# dwengo-1_1.net
KiCad netlist of a schematic drawn in EAGLE
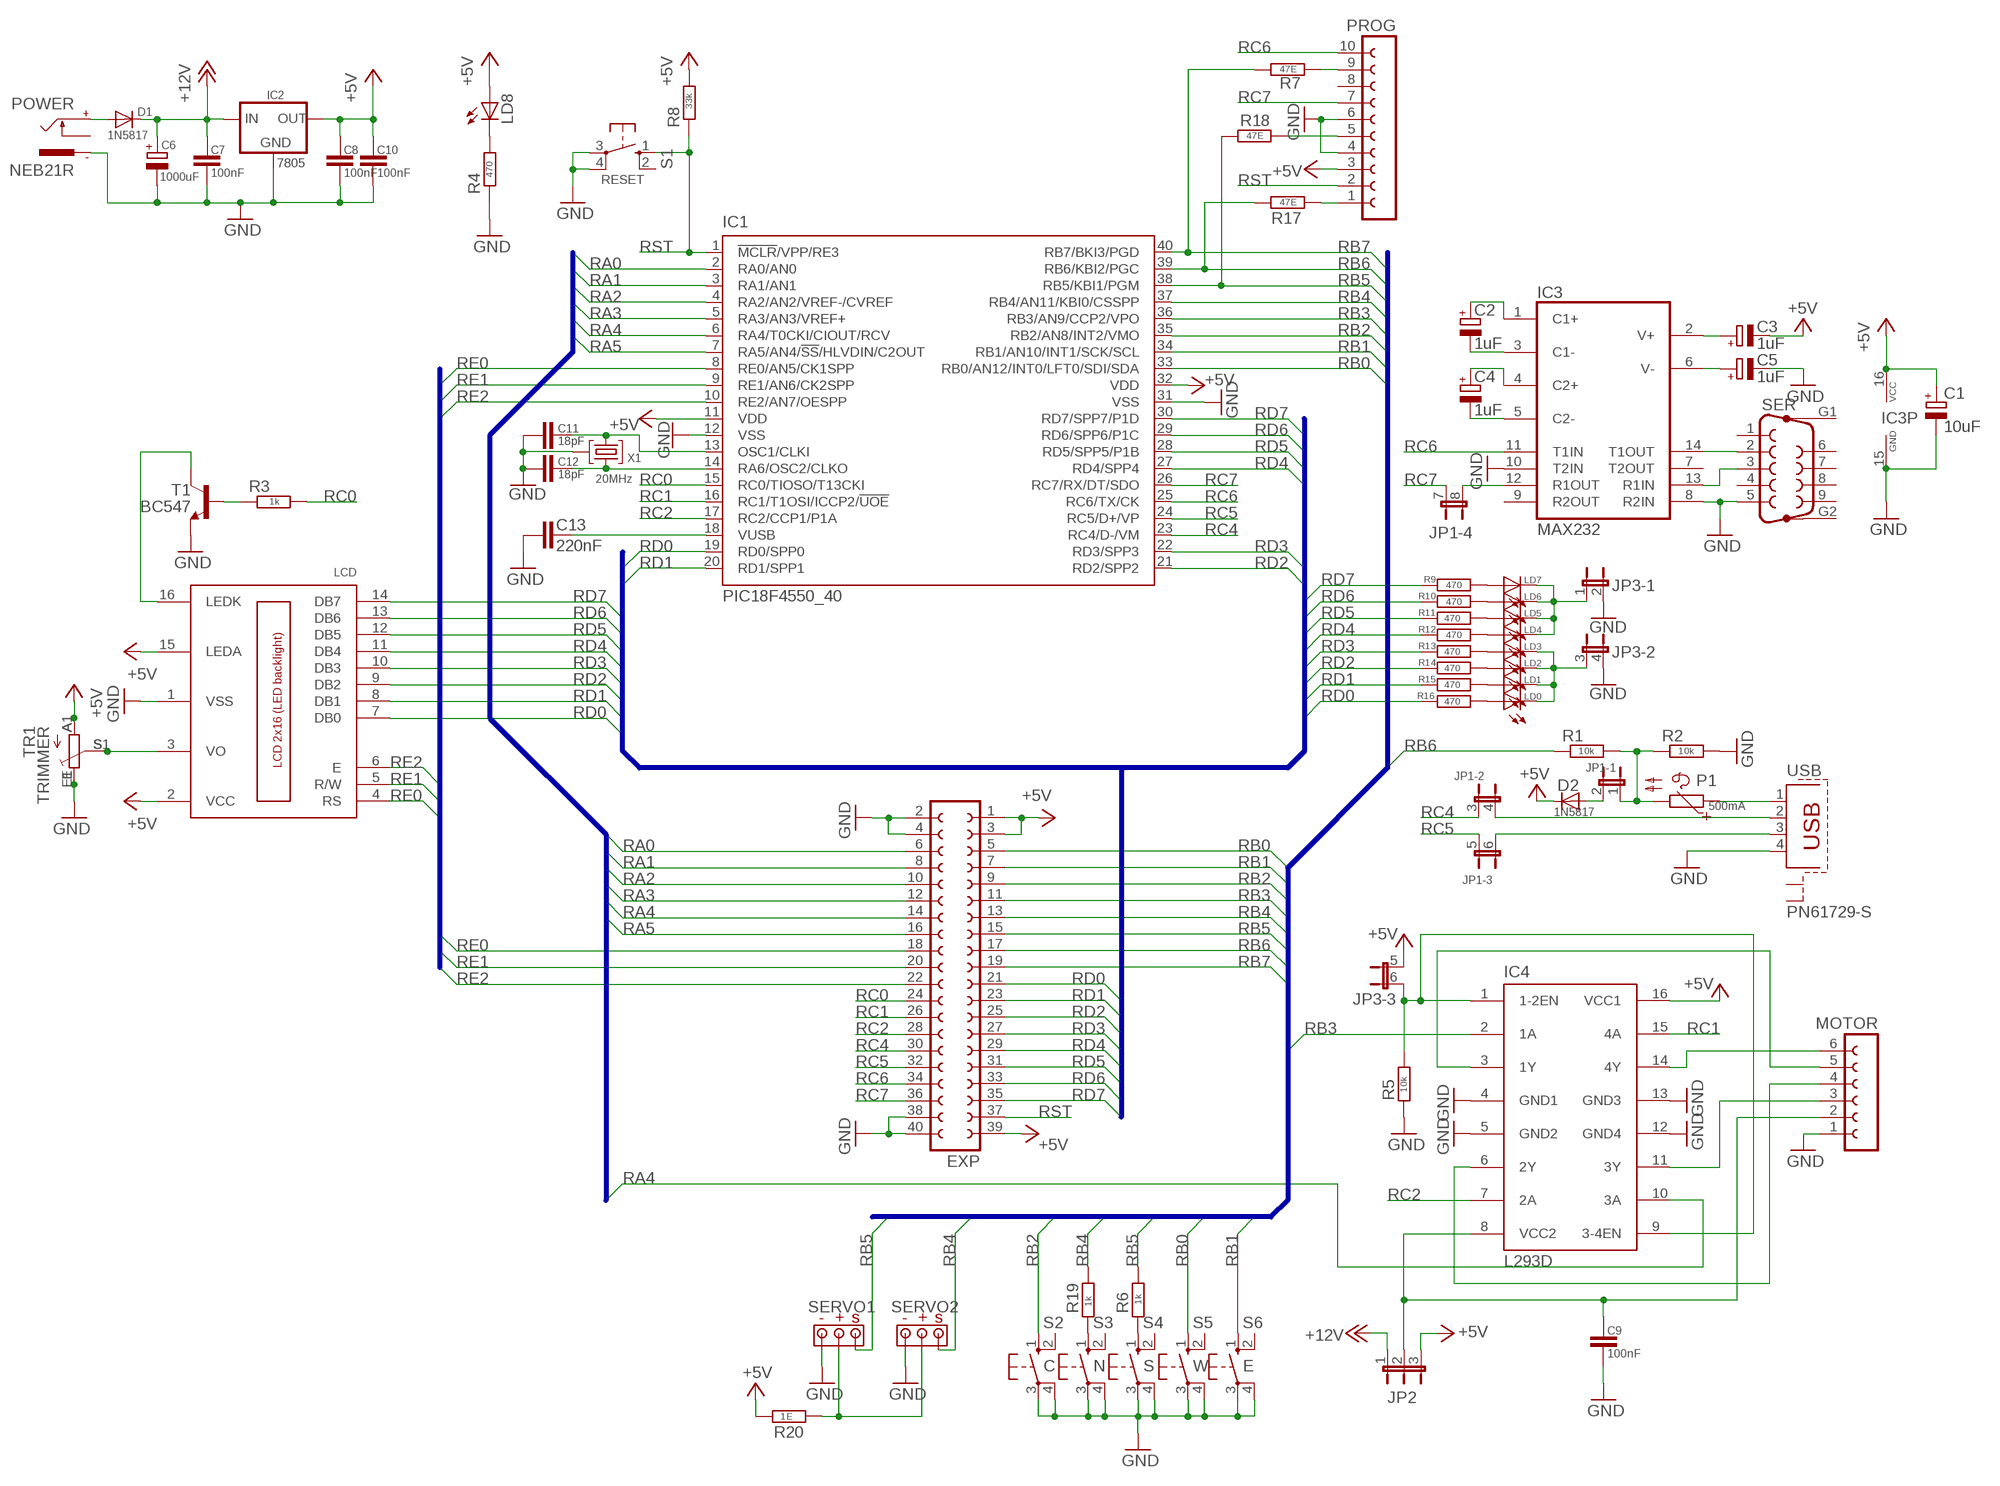
[diagram p0: schematic, sheet 1]

(export (version "E")
  (design (tool "Eeschema 10.0.6"))
  (components
    (comp (ref "C1")
      (value "10uF")
      (footprint "eagle-import:E2-5")
      (libsource (lib "eagle-import") (part "CPOL-EUE2-5"))
    )
    (comp (ref "C2")
      (value "1uF")
      (footprint "eagle-import:E2-5")
      (libsource (lib "eagle-import") (part "CPOL-EUE2-5"))
    )
    (comp (ref "C3")
      (value "1uF")
      (footprint "eagle-import:E2-5")
      (libsource (lib "eagle-import") (part "CPOL-EUE2-5"))
    )
    (comp (ref "C4")
      (value "1uF")
      (footprint "eagle-import:E2-5")
      (libsource (lib "eagle-import") (part "CPOL-EUE2-5"))
    )
    (comp (ref "C5")
      (value "1uF")
      (footprint "eagle-import:E2-5")
      (libsource (lib "eagle-import") (part "CPOL-EUE2-5"))
    )
    (comp (ref "C6")
      (value "1000uF")
      (footprint "eagle-import:E5-10,5")
      (libsource (lib "eagle-import") (part "CPOL-EUE5-10.5"))
    )
    (comp (ref "C7")
      (value "100nF")
      (footprint "eagle-import:C-EU050-025X075")
      (libsource (lib "eagle-import") (part "C-EU050-025X075"))
    )
    (comp (ref "C8")
      (value "100nF")
      (footprint "eagle-import:C-EU050-025X075")
      (libsource (lib "eagle-import") (part "C-EU050-025X075"))
    )
    (comp (ref "C9")
      (value "100nF")
      (footprint "eagle-import:C-EU050-025X075")
      (libsource (lib "eagle-import") (part "C-EU050-025X075"))
    )
    (comp (ref "C10")
      (value "100nF")
      (footprint "eagle-import:C-EU050-025X075")
      (libsource (lib "eagle-import") (part "C-EU050-025X075"))
    )
    (comp (ref "C11")
      (value "18pF")
      (footprint "eagle-import:C-EU050-024X044")
      (libsource (lib "eagle-import") (part "C-EU050-024X044"))
    )
    (comp (ref "C12")
      (value "18pF")
      (footprint "eagle-import:C-EU050-024X044")
      (libsource (lib "eagle-import") (part "C-EU050-024X044"))
    )
    (comp (ref "C13")
      (value "220nF")
      (footprint "eagle-import:C-EU050-035X075")
      (libsource (lib "eagle-import") (part "C-EU050-035X075"))
    )
    (comp (ref "D1")
      (value "1N5817")
      (footprint "eagle-import:DO41-10")
      (libsource (lib "eagle-import") (part "1N4004"))
    )
    (comp (ref "D2")
      (value "1N5817")
      (footprint "eagle-import:DO41-10")
      (libsource (lib "eagle-import") (part "1N4004"))
    )
    (comp (ref "EXP")
      (value "FE20-2W")
      (footprint "eagle-import:FE20-2W")
      (libsource (lib "eagle-import") (part "FE20-2W"))
    )
    (comp (ref "IC1")
      (value "PIC18F4550_40")
      (footprint "eagle-import:DIL40")
      (libsource (lib "eagle-import") (part "PIC18F4_40455"))
    )
    (comp (ref "IC2")
      (value "7805")
      (footprint "eagle-import:78XXS")
      (libsource (lib "eagle-import") (part "78XXS"))
    )
    (comp (ref "IC3")
      (value "MAX232")
      (footprint "eagle-import:DIL16")
      (libsource (lib "eagle-import") (part "MAX232"))
    )
    (comp (ref "IC4")
      (value "L293D")
      (footprint "eagle-import:DIL16")
      (libsource (lib "eagle-import") (part "L293D"))
    )
    (comp (ref "JP1")
      (value "JP2_4")
      (footprint "eagle-import:JP2_4")
      (libsource (lib "eagle-import") (part "JP2_4"))
    )
    (comp (ref "JP2")
      (value "JP_3MOTOR")
      (footprint "eagle-import:JP_MOTOR")
      (libsource (lib "eagle-import") (part "JP_3MOTOR"))
    )
    (comp (ref "JP3")
      (value "JP3QE")
      (footprint "eagle-import:JP3Q")
      (libsource (lib "eagle-import") (part "JP3QE"))
    )
    (comp (ref "LCD")
      (value "LCD_2X16")
      (footprint "eagle-import:HY-1602F")
      (libsource (lib "eagle-import") (part "LCD_2X16"))
    )
    (comp (ref "LD0")
      (value "LED3MM")
      (footprint "eagle-import:LED3MM")
      (libsource (lib "eagle-import") (part "LED3MM"))
    )
    (comp (ref "LD1")
      (value "LED3MM")
      (footprint "eagle-import:LED3MM")
      (libsource (lib "eagle-import") (part "LED3MM"))
    )
    (comp (ref "LD2")
      (value "LED3MM")
      (footprint "eagle-import:LED3MM")
      (libsource (lib "eagle-import") (part "LED3MM"))
    )
    (comp (ref "LD3")
      (value "LED3MM")
      (footprint "eagle-import:LED3MM")
      (libsource (lib "eagle-import") (part "LED3MM"))
    )
    (comp (ref "LD4")
      (value "LED3MM")
      (footprint "eagle-import:LED3MM")
      (libsource (lib "eagle-import") (part "LED3MM"))
    )
    (comp (ref "LD5")
      (value "LED3MM")
      (footprint "eagle-import:LED3MM")
      (libsource (lib "eagle-import") (part "LED3MM"))
    )
    (comp (ref "LD6")
      (value "LED3MM")
      (footprint "eagle-import:LED3MM")
      (libsource (lib "eagle-import") (part "LED3MM"))
    )
    (comp (ref "LD7")
      (value "LED3MM")
      (footprint "eagle-import:LED3MM")
      (libsource (lib "eagle-import") (part "LED3MM"))
    )
    (comp (ref "LD8")
      (value "LED3MM")
      (footprint "eagle-import:LED3MM")
      (libsource (lib "eagle-import") (part "LED3MM"))
    )
    (comp (ref "MOTOR")
      (value "MOTOR")
      (footprint "eagle-import:MOTOR")
      (libsource (lib "eagle-import") (part "MOTOR"))
    )
    (comp (ref "P1")
      (value "500mA")
      (footprint "eagle-import:POLYSWITCH")
      (libsource (lib "eagle-import") (part "POLYSWITCH"))
    )
    (comp (ref "POWER")
      (value "NEB21R")
      (footprint "eagle-import:NEB21R")
      (libsource (lib "eagle-import") (part "NEB21R"))
    )
    (comp (ref "PROG")
      (value "PROG_CONNECTOR")
      (footprint "eagle-import:PROG_CONNECTOR")
      (libsource (lib "eagle-import") (part "PROG_CONNECTOR"))
    )
    (comp (ref "R1")
      (value "10k")
      (footprint "eagle-import:0204_7")
      (libsource (lib "eagle-import") (part "R-EU_0204/7"))
    )
    (comp (ref "R2")
      (value "10k")
      (footprint "eagle-import:0204_7")
      (libsource (lib "eagle-import") (part "R-EU_0204/7"))
    )
    (comp (ref "R3")
      (value "1k")
      (footprint "eagle-import:0204_7")
      (libsource (lib "eagle-import") (part "R-EU_0204/7"))
    )
    (comp (ref "R4")
      (value "470")
      (footprint "eagle-import:0204_7")
      (libsource (lib "eagle-import") (part "R-EU_0204/7"))
    )
    (comp (ref "R5")
      (value "10k")
      (footprint "eagle-import:0204_7")
      (libsource (lib "eagle-import") (part "R-EU_0204/7"))
    )
    (comp (ref "R6")
      (value "1k")
      (footprint "eagle-import:0204_7")
      (libsource (lib "eagle-import") (part "R-EU_0204/7"))
    )
    (comp (ref "R7")
      (value "47E")
      (footprint "eagle-import:0204_7")
      (libsource (lib "eagle-import") (part "R-EU_0204/7"))
    )
    (comp (ref "R8")
      (value "33k")
      (footprint "eagle-import:0204_7")
      (libsource (lib "eagle-import") (part "R-EU_0204/7"))
    )
    (comp (ref "R9")
      (value "470")
      (footprint "eagle-import:0204_7")
      (libsource (lib "eagle-import") (part "R-EU_0204/7"))
    )
    (comp (ref "R10")
      (value "470")
      (footprint "eagle-import:0204_7")
      (libsource (lib "eagle-import") (part "R-EU_0204/7"))
    )
    (comp (ref "R11")
      (value "470")
      (footprint "eagle-import:0204_7")
      (libsource (lib "eagle-import") (part "R-EU_0204/7"))
    )
    (comp (ref "R12")
      (value "470")
      (footprint "eagle-import:0204_7")
      (libsource (lib "eagle-import") (part "R-EU_0204/7"))
    )
    (comp (ref "R13")
      (value "470")
      (footprint "eagle-import:0204_7")
      (libsource (lib "eagle-import") (part "R-EU_0204/7"))
    )
    (comp (ref "R14")
      (value "470")
      (footprint "eagle-import:0204_7")
      (libsource (lib "eagle-import") (part "R-EU_0204/7"))
    )
    (comp (ref "R15")
      (value "470")
      (footprint "eagle-import:0204_7")
      (libsource (lib "eagle-import") (part "R-EU_0204/7"))
    )
    (comp (ref "R16")
      (value "470")
      (footprint "eagle-import:0204_7")
      (libsource (lib "eagle-import") (part "R-EU_0204/7"))
    )
    (comp (ref "R17")
      (value "47E")
      (footprint "eagle-import:0204_7")
      (libsource (lib "eagle-import") (part "R-EU_0204/7"))
    )
    (comp (ref "R18")
      (value "47E")
      (footprint "eagle-import:0204_7")
      (libsource (lib "eagle-import") (part "R-EU_0204/7"))
    )
    (comp (ref "R19")
      (value "1k")
      (footprint "eagle-import:0204_7")
      (libsource (lib "eagle-import") (part "R-EU_0204/7"))
    )
    (comp (ref "R20")
      (value "1E")
      (footprint "eagle-import:0204_7")
      (libsource (lib "eagle-import") (part "R-EU_0204/7"))
    )
    (comp (ref "S1")
      (value "10-XX")
      (footprint "eagle-import:B3F-10XX")
      (libsource (lib "eagle-import") (part "10-XX"))
    )
    (comp (ref "S2")
      (value "10-XX")
      (footprint "eagle-import:B3F-10XX")
      (libsource (lib "eagle-import") (part "10-XX"))
    )
    (comp (ref "S3")
      (value "10-XX")
      (footprint "eagle-import:B3F-10XX")
      (libsource (lib "eagle-import") (part "10-XX"))
    )
    (comp (ref "S4")
      (value "10-XX")
      (footprint "eagle-import:B3F-10XX")
      (libsource (lib "eagle-import") (part "10-XX"))
    )
    (comp (ref "S5")
      (value "10-XX")
      (footprint "eagle-import:B3F-10XX")
      (libsource (lib "eagle-import") (part "10-XX"))
    )
    (comp (ref "S6")
      (value "10-XX")
      (footprint "eagle-import:B3F-10XX")
      (libsource (lib "eagle-import") (part "10-XX"))
    )
    (comp (ref "SER")
      (value "F09HP")
      (footprint "eagle-import:F09HP")
      (libsource (lib "eagle-import") (part "F09HP"))
    )
    (comp (ref "SERVO1")
      (value "SERVO")
      (footprint "eagle-import:SERVO")
      (libsource (lib "eagle-import") (part "SERVO"))
    )
    (comp (ref "SERVO2")
      (value "SERVO")
      (footprint "eagle-import:SERVO")
      (libsource (lib "eagle-import") (part "SERVO"))
    )
    (comp (ref "T1")
      (value "BC547")
      (footprint "eagle-import:TO92")
      (libsource (lib "eagle-import") (part "BC547"))
    )
    (comp (ref "TR1")
      (value "TRIMMER")
      (footprint "eagle-import:TRIMMER")
      (libsource (lib "eagle-import") (part "TRIMMER"))
    )
    (comp (ref "USB")
      (value "PN61729-S")
      (footprint "eagle-import:PN61729-S")
      (libsource (lib "eagle-import") (part "PN61729-S"))
    )
    (comp (ref "X1")
      (value "20MHz")
      (footprint "eagle-import:CRYSTAL_RES")
      (libsource (lib "eagle-import") (part "CRYSTAL_RES"))
    )
  )
  (nets
    (net (code "1") (name "+5V") (class "Default")
      (node (ref "C1") (pin "+") (pinfunction "+_+") (pintype "passive"))
      (node (ref "C10") (pin "2") (pinfunction "2_2") (pintype "passive"))
      (node (ref "C3") (pin "-") (pinfunction "-_-") (pintype "passive"))
      (node (ref "C8") (pin "2") (pinfunction "2_2") (pintype "passive"))
      (node (ref "D2") (pin "C") (pinfunction "C_C") (pintype "passive"))
      (node (ref "EXP") (pin "1") (pinfunction "1_1") (pintype "passive"))
      (node (ref "EXP") (pin "3") (pinfunction "3_3") (pintype "passive"))
      (node (ref "EXP") (pin "39") (pinfunction "39_39") (pintype "passive"))
      (node (ref "IC1") (pin "11") (pinfunction "VDD_11") (pintype "power_in"))
      (node (ref "IC1") (pin "32") (pinfunction "VDD_32") (pintype "power_in"))
      (node (ref "IC2") (pin "OUT") (pinfunction "OUT_OUT") (pintype "passive"))
      (node (ref "IC3") (pin "16") (pinfunction "VCC_16") (pintype "power_in"))
      (node (ref "IC4") (pin "16") (pinfunction "VCC1_16") (pintype "power_in"))
      (node (ref "JP2") (pin "3") (pinfunction "3_3") (pintype "passive"))
      (node (ref "JP3") (pin "5") (pinfunction "1_5") (pintype "passive"))
      (node (ref "LCD") (pin "15") (pinfunction "LEDA_15") (pintype "passive"))
      (node (ref "LCD") (pin "2") (pinfunction "VCC_2") (pintype "power_in"))
      (node (ref "LD8") (pin "A") (pinfunction "A_A") (pintype "passive"))
      (node (ref "PROG") (pin "3") (pinfunction "3_3") (pintype "passive"))
      (node (ref "R20") (pin "1") (pinfunction "1_1") (pintype "passive"))
      (node (ref "R8") (pin "2") (pinfunction "2_2") (pintype "passive"))
      (node (ref "TR1") (pin "A") (pinfunction "A_A") (pintype "passive"))
      (node (ref "TR1") (pin "A1") (pinfunction "A1_A1") (pintype "passive"))
    )
    (net (code "2") (name "+12V") (class "Default")
      (node (ref "C6") (pin "+") (pinfunction "+_+") (pintype "passive"))
      (node (ref "C7") (pin "2") (pinfunction "2_2") (pintype "passive"))
      (node (ref "D1") (pin "C") (pinfunction "C_C") (pintype "passive"))
      (node (ref "IC2") (pin "IN") (pinfunction "IN_IN") (pintype "input"))
      (node (ref "JP2") (pin "1") (pinfunction "1_1") (pintype "passive"))
    )
    (net (code "3") (name "/RA0") (class "Default")
      (node (ref "EXP") (pin "6") (pinfunction "6_6") (pintype "passive"))
      (node (ref "IC1") (pin "2") (pinfunction "RA0/AN0_2") (pintype "bidirectional"))
    )
    (net (code "4") (name "/RA1") (class "Default")
      (node (ref "EXP") (pin "8") (pinfunction "8_8") (pintype "passive"))
      (node (ref "IC1") (pin "3") (pinfunction "RA1/AN1_3") (pintype "bidirectional"))
    )
    (net (code "5") (name "/RA2") (class "Default")
      (node (ref "EXP") (pin "10") (pinfunction "10_10") (pintype "passive"))
      (node (ref "IC1") (pin "4") (pinfunction "RA2/AN2/VREF-/CVREF_4") (pintype "bidirectional"))
    )
    (net (code "6") (name "/RA3") (class "Default")
      (node (ref "EXP") (pin "12") (pinfunction "12_12") (pintype "passive"))
      (node (ref "IC1") (pin "5") (pinfunction "RA3/AN3/VREF+_5") (pintype "bidirectional"))
    )
    (net (code "7") (name "/RA4") (class "Default")
      (node (ref "EXP") (pin "14") (pinfunction "14_14") (pintype "passive"))
      (node (ref "IC1") (pin "6") (pinfunction "RA4/T0CKI/CIOUT/RCV_6") (pintype "bidirectional"))
      (node (ref "IC4") (pin "10") (pinfunction "3A_10") (pintype "input"))
    )
    (net (code "8") (name "/RA5") (class "Default")
      (node (ref "EXP") (pin "16") (pinfunction "16_16") (pintype "passive"))
      (node (ref "IC1") (pin "7") (pinfunction "RA5/AN4/~{SS}/HLVDIN/C2OUT_7") (pintype "bidirectional"))
    )
    (net (code "9") (name "/RB0") (class "Default")
      (node (ref "EXP") (pin "5") (pinfunction "5_5") (pintype "passive"))
      (node (ref "IC1") (pin "33") (pinfunction "RB0/AN12/INT0/LFT0/SDI/SDA_33") (pintype "bidirectional"))
      (node (ref "S5") (pin "1") (pinfunction "S_1") (pintype "passive"))
    )
    (net (code "10") (name "/RB1") (class "Default")
      (node (ref "EXP") (pin "7") (pinfunction "7_7") (pintype "passive"))
      (node (ref "IC1") (pin "34") (pinfunction "RB1/AN10/INT1/SCK/SCL_34") (pintype "bidirectional"))
      (node (ref "S6") (pin "1") (pinfunction "S_1") (pintype "passive"))
    )
    (net (code "11") (name "/RB2") (class "Default")
      (node (ref "EXP") (pin "9") (pinfunction "9_9") (pintype "passive"))
      (node (ref "IC1") (pin "35") (pinfunction "RB2/AN8/INT2/VMO_35") (pintype "bidirectional"))
      (node (ref "S2") (pin "1") (pinfunction "S_1") (pintype "passive"))
    )
    (net (code "12") (name "/RB3") (class "Default")
      (node (ref "EXP") (pin "11") (pinfunction "11_11") (pintype "passive"))
      (node (ref "IC1") (pin "36") (pinfunction "RB3/AN9/CCP2/VPO_36") (pintype "bidirectional"))
      (node (ref "IC4") (pin "2") (pinfunction "1A_2") (pintype "input"))
    )
    (net (code "13") (name "/RB4") (class "Default")
      (node (ref "EXP") (pin "13") (pinfunction "13_13") (pintype "passive"))
      (node (ref "IC1") (pin "37") (pinfunction "RB4/AN11/KBI0/CSSPP_37") (pintype "bidirectional"))
      (node (ref "R19") (pin "2") (pinfunction "2_2") (pintype "passive"))
      (node (ref "SERVO2") (pin "S") (pinfunction "S_S") (pintype "passive"))
    )
    (net (code "14") (name "/RB5") (class "Default")
      (node (ref "EXP") (pin "15") (pinfunction "15_15") (pintype "passive"))
      (node (ref "IC1") (pin "38") (pinfunction "RB5/KBI1/PGM_38") (pintype "bidirectional"))
      (node (ref "R18") (pin "1") (pinfunction "1_1") (pintype "passive"))
      (node (ref "R6") (pin "2") (pinfunction "2_2") (pintype "passive"))
      (node (ref "SERVO1") (pin "S") (pinfunction "S_S") (pintype "passive"))
    )
    (net (code "15") (name "/RB6") (class "Default")
      (node (ref "EXP") (pin "17") (pinfunction "17_17") (pintype "passive"))
      (node (ref "IC1") (pin "39") (pinfunction "RB6/KBI2/PGC_39") (pintype "bidirectional"))
      (node (ref "R1") (pin "2") (pinfunction "2_2") (pintype "passive"))
      (node (ref "R17") (pin "1") (pinfunction "1_1") (pintype "passive"))
    )
    (net (code "16") (name "/RB7") (class "Default")
      (node (ref "EXP") (pin "19") (pinfunction "19_19") (pintype "passive"))
      (node (ref "IC1") (pin "40") (pinfunction "RB7/BKI3/PGD_40") (pintype "bidirectional"))
      (node (ref "R7") (pin "1") (pinfunction "1_1") (pintype "passive"))
    )
    (net (code "17") (name "/RC0") (class "Default")
      (node (ref "EXP") (pin "24") (pinfunction "24_24") (pintype "passive"))
      (node (ref "IC1") (pin "15") (pinfunction "RC0/TIOSO/T13CKI_15") (pintype "bidirectional"))
      (node (ref "R3") (pin "2") (pinfunction "2_2") (pintype "passive"))
    )
    (net (code "18") (name "/RC1") (class "Default")
      (node (ref "EXP") (pin "26") (pinfunction "26_26") (pintype "passive"))
      (node (ref "IC1") (pin "16") (pinfunction "RC1/T1OSI/ICCP2/~{UOE}_16") (pintype "bidirectional"))
      (node (ref "IC4") (pin "15") (pinfunction "4A_15") (pintype "input"))
    )
    (net (code "19") (name "/RC2") (class "Default")
      (node (ref "EXP") (pin "28") (pinfunction "28_28") (pintype "passive"))
      (node (ref "IC1") (pin "17") (pinfunction "RC2/CCP1/P1A_17") (pintype "bidirectional"))
      (node (ref "IC4") (pin "7") (pinfunction "2A_7") (pintype "input"))
    )
    (net (code "20") (name "/RC4") (class "Default")
      (node (ref "EXP") (pin "30") (pinfunction "30_30") (pintype "passive"))
      (node (ref "IC1") (pin "23") (pinfunction "RC4/D-/VM_23") (pintype "bidirectional"))
      (node (ref "JP1") (pin "3") (pinfunction "1_3") (pintype "passive"))
    )
    (net (code "21") (name "/RC5") (class "Default")
      (node (ref "EXP") (pin "32") (pinfunction "32_32") (pintype "passive"))
      (node (ref "IC1") (pin "24") (pinfunction "RC5/D+/VP_24") (pintype "bidirectional"))
      (node (ref "JP1") (pin "5") (pinfunction "1_5") (pintype "passive"))
    )
    (net (code "22") (name "/RC6") (class "Default")
      (node (ref "EXP") (pin "34") (pinfunction "34_34") (pintype "passive"))
      (node (ref "IC1") (pin "25") (pinfunction "RC6/TX/CK_25") (pintype "bidirectional"))
      (node (ref "IC3") (pin "11") (pinfunction "T1IN_11") (pintype "input"))
      (node (ref "PROG") (pin "10") (pinfunction "10_10") (pintype "passive"))
    )
    (net (code "23") (name "/RC7") (class "Default")
      (node (ref "EXP") (pin "36") (pinfunction "36_36") (pintype "passive"))
      (node (ref "IC1") (pin "26") (pinfunction "RC7/RX/DT/SDO_26") (pintype "bidirectional"))
      (node (ref "JP1") (pin "7") (pinfunction "1_7") (pintype "passive"))
      (node (ref "PROG") (pin "7") (pinfunction "7_7") (pintype "passive"))
    )
    (net (code "24") (name "/RD0") (class "Default")
      (node (ref "EXP") (pin "21") (pinfunction "21_21") (pintype "passive"))
      (node (ref "IC1") (pin "19") (pinfunction "RD0/SPP0_19") (pintype "bidirectional"))
      (node (ref "LCD") (pin "7") (pinfunction "DB0_7") (pintype "bidirectional"))
      (node (ref "R16") (pin "1") (pinfunction "1_1") (pintype "passive"))
    )
    (net (code "25") (name "/RD1") (class "Default")
      (node (ref "EXP") (pin "23") (pinfunction "23_23") (pintype "passive"))
      (node (ref "IC1") (pin "20") (pinfunction "RD1/SPP1_20") (pintype "bidirectional"))
      (node (ref "LCD") (pin "8") (pinfunction "DB1_8") (pintype "bidirectional"))
      (node (ref "R15") (pin "1") (pinfunction "1_1") (pintype "passive"))
    )
    (net (code "26") (name "/RD2") (class "Default")
      (node (ref "EXP") (pin "25") (pinfunction "25_25") (pintype "passive"))
      (node (ref "IC1") (pin "21") (pinfunction "RD2/SPP2_21") (pintype "bidirectional"))
      (node (ref "LCD") (pin "9") (pinfunction "DB2_9") (pintype "bidirectional"))
      (node (ref "R14") (pin "1") (pinfunction "1_1") (pintype "passive"))
    )
    (net (code "27") (name "/RD3") (class "Default")
      (node (ref "EXP") (pin "27") (pinfunction "27_27") (pintype "passive"))
      (node (ref "IC1") (pin "22") (pinfunction "RD3/SPP3_22") (pintype "bidirectional"))
      (node (ref "LCD") (pin "10") (pinfunction "DB3_10") (pintype "bidirectional"))
      (node (ref "R13") (pin "1") (pinfunction "1_1") (pintype "passive"))
    )
    (net (code "28") (name "/RD4") (class "Default")
      (node (ref "EXP") (pin "29") (pinfunction "29_29") (pintype "passive"))
      (node (ref "IC1") (pin "27") (pinfunction "RD4/SPP4_27") (pintype "bidirectional"))
      (node (ref "LCD") (pin "11") (pinfunction "DB4_11") (pintype "bidirectional"))
      (node (ref "R12") (pin "1") (pinfunction "1_1") (pintype "passive"))
    )
    (net (code "29") (name "/RD5") (class "Default")
      (node (ref "EXP") (pin "31") (pinfunction "31_31") (pintype "passive"))
      (node (ref "IC1") (pin "28") (pinfunction "RD5/SPP5/P1B_28") (pintype "bidirectional"))
      (node (ref "LCD") (pin "12") (pinfunction "DB5_12") (pintype "bidirectional"))
      (node (ref "R11") (pin "1") (pinfunction "1_1") (pintype "passive"))
    )
    (net (code "30") (name "/RD6") (class "Default")
      (node (ref "EXP") (pin "33") (pinfunction "33_33") (pintype "passive"))
      (node (ref "IC1") (pin "29") (pinfunction "RD6/SPP6/P1C_29") (pintype "bidirectional"))
      (node (ref "LCD") (pin "13") (pinfunction "DB6_13") (pintype "bidirectional"))
      (node (ref "R10") (pin "1") (pinfunction "1_1") (pintype "passive"))
    )
    (net (code "31") (name "/RD7") (class "Default")
      (node (ref "EXP") (pin "35") (pinfunction "35_35") (pintype "passive"))
      (node (ref "IC1") (pin "30") (pinfunction "RD7/SPP7/P1D_30") (pintype "bidirectional"))
      (node (ref "LCD") (pin "14") (pinfunction "DB7_14") (pintype "bidirectional"))
      (node (ref "R9") (pin "1") (pinfunction "1_1") (pintype "passive"))
    )
    (net (code "32") (name "/RE0") (class "Default")
      (node (ref "EXP") (pin "18") (pinfunction "18_18") (pintype "passive"))
      (node (ref "IC1") (pin "8") (pinfunction "RE0/AN5/CK1SPP_8") (pintype "bidirectional"))
      (node (ref "LCD") (pin "4") (pinfunction "RS_4") (pintype "input"))
    )
    (net (code "33") (name "/RE1") (class "Default")
      (node (ref "EXP") (pin "20") (pinfunction "20_20") (pintype "passive"))
      (node (ref "IC1") (pin "9") (pinfunction "RE1/AN6/CK2SPP_9") (pintype "bidirectional"))
      (node (ref "LCD") (pin "5") (pinfunction "R/W_5") (pintype "input"))
    )
    (net (code "34") (name "/RE2") (class "Default")
      (node (ref "EXP") (pin "22") (pinfunction "22_22") (pintype "passive"))
      (node (ref "IC1") (pin "10") (pinfunction "RE2/AN7/OESPP_10") (pintype "bidirectional"))
      (node (ref "LCD") (pin "6") (pinfunction "E_6") (pintype "input"))
    )
    (net (code "35") (name "/RST") (class "Default")
      (node (ref "EXP") (pin "37") (pinfunction "37_37") (pintype "passive"))
      (node (ref "IC1") (pin "1") (pinfunction "~{MCLR}/VPP/RE3_1") (pintype "input"))
      (node (ref "PROG") (pin "2") (pinfunction "2_2") (pintype "passive"))
      (node (ref "R8") (pin "1") (pinfunction "1_1") (pintype "passive"))
      (node (ref "S1") (pin "1") (pinfunction "S_1") (pintype "passive"))
    )
    (net (code "36") (name "GND") (class "Default")
      (node (ref "C1") (pin "-") (pinfunction "-_-") (pintype "passive"))
      (node (ref "C10") (pin "1") (pinfunction "1_1") (pintype "passive"))
      (node (ref "C11") (pin "2") (pinfunction "2_2") (pintype "passive"))
      (node (ref "C12") (pin "2") (pinfunction "2_2") (pintype "passive"))
      (node (ref "C13") (pin "2") (pinfunction "2_2") (pintype "passive"))
      (node (ref "C5") (pin "-") (pinfunction "-_-") (pintype "passive"))
      (node (ref "C6") (pin "-") (pinfunction "-_-") (pintype "passive"))
      (node (ref "C7") (pin "1") (pinfunction "1_1") (pintype "passive"))
      (node (ref "C8") (pin "1") (pinfunction "1_1") (pintype "passive"))
      (node (ref "C9") (pin "1") (pinfunction "1_1") (pintype "passive"))
      (node (ref "EXP") (pin "2") (pinfunction "2_2") (pintype "passive"))
      (node (ref "EXP") (pin "38") (pinfunction "38_38") (pintype "passive"))
      (node (ref "EXP") (pin "4") (pinfunction "4_4") (pintype "passive"))
      (node (ref "EXP") (pin "40") (pinfunction "40_40") (pintype "passive"))
      (node (ref "IC1") (pin "12") (pinfunction "VSS_12") (pintype "power_in"))
      (node (ref "IC1") (pin "31") (pinfunction "VSS_31") (pintype "power_in"))
      (node (ref "IC2") (pin "GND") (pinfunction "GND_GND") (pintype "input"))
      (node (ref "IC3") (pin "10") (pinfunction "T2IN_10") (pintype "input"))
      (node (ref "IC3") (pin "15") (pinfunction "GND_15") (pintype "power_in"))
      (node (ref "IC3") (pin "8") (pinfunction "R2IN_8") (pintype "input"))
      (node (ref "IC4") (pin "12") (pinfunction "GND4_12") (pintype "power_in"))
      (node (ref "IC4") (pin "13") (pinfunction "GND3_13") (pintype "power_in"))
      (node (ref "IC4") (pin "4") (pinfunction "GND1_4") (pintype "power_in"))
      (node (ref "IC4") (pin "5") (pinfunction "GND2_5") (pintype "power_in"))
      (node (ref "JP3") (pin "2") (pinfunction "2_2") (pintype "passive"))
      (node (ref "JP3") (pin "4") (pinfunction "2_4") (pintype "passive"))
      (node (ref "LCD") (pin "1") (pinfunction "VSS_1") (pintype "power_in"))
      (node (ref "MOTOR") (pin "1") (pinfunction "1_1") (pintype "passive"))
      (node (ref "POWER") (pin "-") (pinfunction "-_-") (pintype "passive"))
      (node (ref "PROG") (pin "4") (pinfunction "4_4") (pintype "passive"))
      (node (ref "PROG") (pin "6") (pinfunction "6_6") (pintype "passive"))
      (node (ref "R2") (pin "2") (pinfunction "2_2") (pintype "passive"))
      (node (ref "R4") (pin "1") (pinfunction "1_1") (pintype "passive"))
      (node (ref "R5") (pin "1") (pinfunction "1_1") (pintype "passive"))
      (node (ref "S1") (pin "3") (pinfunction "P_3") (pintype "passive"))
      (node (ref "S1") (pin "4") (pinfunction "P1_4") (pintype "passive"))
      (node (ref "S2") (pin "3") (pinfunction "P_3") (pintype "passive"))
      (node (ref "S2") (pin "4") (pinfunction "P1_4") (pintype "passive"))
      (node (ref "S3") (pin "3") (pinfunction "P_3") (pintype "passive"))
      (node (ref "S3") (pin "4") (pinfunction "P1_4") (pintype "passive"))
      (node (ref "S4") (pin "3") (pinfunction "P_3") (pintype "passive"))
      (node (ref "S4") (pin "4") (pinfunction "P1_4") (pintype "passive"))
      (node (ref "S5") (pin "3") (pinfunction "P_3") (pintype "passive"))
      (node (ref "S5") (pin "4") (pinfunction "P1_4") (pintype "passive"))
      (node (ref "S6") (pin "3") (pinfunction "P_3") (pintype "passive"))
      (node (ref "S6") (pin "4") (pinfunction "P1_4") (pintype "passive"))
      (node (ref "SER") (pin "5") (pinfunction "5_5") (pintype "passive"))
      (node (ref "SERVO1") (pin "-") (pinfunction "-_-") (pintype "passive"))
      (node (ref "SERVO2") (pin "-") (pinfunction "-_-") (pintype "passive"))
      (node (ref "T1") (pin "1") (pinfunction "E_1") (pintype "passive"))
      (node (ref "TR1") (pin "E") (pinfunction "E_E") (pintype "passive"))
      (node (ref "TR1") (pin "E1") (pinfunction "E1_E1") (pintype "passive"))
      (node (ref "USB") (pin "4") (pinfunction "4_4") (pintype "passive"))
      (node (ref "X1") (pin "P$1") (pinfunction "3_P$1") (pintype "passive"))
    )
    (net (code "37") (name "Net-(D1-PadA)") (class "Default")
      (node (ref "D1") (pin "A") (pinfunction "A_A") (pintype "passive"))
      (node (ref "POWER") (pin "+") (pinfunction "+_+") (pintype "passive"))
    )
    (net (code "38") (name "Net-(D2-PadA)") (class "Default")
      (node (ref "D2") (pin "A") (pinfunction "A_A") (pintype "passive"))
      (node (ref "JP1") (pin "2") (pinfunction "2_2") (pintype "passive"))
    )
    (net (code "39") (name "Net-(IC1-OSC1{slash}CLKI)") (class "Default")
      (node (ref "C11") (pin "1") (pinfunction "1_1") (pintype "passive"))
      (node (ref "IC1") (pin "13") (pinfunction "OSC1/CLKI_13") (pintype "input"))
      (node (ref "X1") (pin "2") (pinfunction "2_2") (pintype "passive"))
    )
    (net (code "40") (name "Net-(IC1-RA6{slash}OSC2{slash}CLKO)") (class "Default")
      (node (ref "C12") (pin "1") (pinfunction "1_1") (pintype "passive"))
      (node (ref "IC1") (pin "14") (pinfunction "RA6/OSC2/CLKO_14") (pintype "output"))
      (node (ref "X1") (pin "1") (pinfunction "1_1") (pintype "passive"))
    )
    (net (code "41") (name "Net-(IC1-VUSB)") (class "Default")
      (node (ref "C13") (pin "1") (pinfunction "1_1") (pintype "passive"))
      (node (ref "IC1") (pin "18") (pinfunction "VUSB_18") (pintype "bidirectional"))
    )
    (net (code "42") (name "Net-(IC3A-C1+)") (class "Default")
      (node (ref "C2") (pin "+") (pinfunction "+_+") (pintype "passive"))
      (node (ref "IC3") (pin "1") (pinfunction "C1+_1") (pintype "bidirectional"))
    )
    (net (code "43") (name "Net-(IC3A-C1-)") (class "Default")
      (node (ref "C2") (pin "-") (pinfunction "-_-") (pintype "passive"))
      (node (ref "IC3") (pin "3") (pinfunction "C1-_3") (pintype "bidirectional"))
    )
    (net (code "44") (name "Net-(IC3A-C2+)") (class "Default")
      (node (ref "C4") (pin "+") (pinfunction "+_+") (pintype "passive"))
      (node (ref "IC3") (pin "4") (pinfunction "C2+_4") (pintype "bidirectional"))
    )
    (net (code "45") (name "Net-(IC3A-C2-)") (class "Default")
      (node (ref "C4") (pin "-") (pinfunction "-_-") (pintype "passive"))
      (node (ref "IC3") (pin "5") (pinfunction "C2-_5") (pintype "bidirectional"))
    )
    (net (code "46") (name "Net-(IC3A-R1IN)") (class "Default")
      (node (ref "IC3") (pin "13") (pinfunction "R1IN_13") (pintype "input"))
      (node (ref "SER") (pin "3") (pinfunction "3_3") (pintype "passive"))
    )
    (net (code "47") (name "Net-(IC3A-R1OUT)") (class "Default")
      (node (ref "IC3") (pin "12") (pinfunction "R1OUT_12") (pintype "output"))
      (node (ref "JP1") (pin "8") (pinfunction "2_8") (pintype "passive"))
    )
    (net (code "48") (name "Net-(IC3A-T1OUT)") (class "Default")
      (node (ref "IC3") (pin "14") (pinfunction "T1OUT_14") (pintype "output"))
      (node (ref "SER") (pin "2") (pinfunction "2_2") (pintype "passive"))
    )
    (net (code "49") (name "Net-(IC3A-V+)") (class "Default")
      (node (ref "C3") (pin "+") (pinfunction "+_+") (pintype "passive"))
      (node (ref "IC3") (pin "2") (pinfunction "V+_2") (pintype "bidirectional"))
    )
    (net (code "50") (name "Net-(IC3A-V-)") (class "Default")
      (node (ref "C5") (pin "+") (pinfunction "+_+") (pintype "passive"))
      (node (ref "IC3") (pin "6") (pinfunction "V-_6") (pintype "bidirectional"))
    )
    (net (code "51") (name "Net-(IC4-1-2EN)") (class "Default")
      (node (ref "IC4") (pin "1") (pinfunction "1-2EN_1") (pintype "input"))
      (node (ref "IC4") (pin "9") (pinfunction "3-4EN_9") (pintype "input"))
      (node (ref "JP3") (pin "6") (pinfunction "2_6") (pintype "passive"))
      (node (ref "R5") (pin "2") (pinfunction "2_2") (pintype "passive"))
    )
    (net (code "52") (name "Net-(IC4-1Y)") (class "Default")
      (node (ref "IC4") (pin "3") (pinfunction "1Y_3") (pintype "output"))
      (node (ref "MOTOR") (pin "5") (pinfunction "5_5") (pintype "passive"))
    )
    (net (code "53") (name "Net-(IC4-2Y)") (class "Default")
      (node (ref "IC4") (pin "6") (pinfunction "2Y_6") (pintype "output"))
      (node (ref "MOTOR") (pin "4") (pinfunction "4_4") (pintype "passive"))
    )
    (net (code "54") (name "Net-(IC4-3Y)") (class "Default")
      (node (ref "IC4") (pin "11") (pinfunction "3Y_11") (pintype "output"))
      (node (ref "MOTOR") (pin "3") (pinfunction "3_3") (pintype "passive"))
    )
    (net (code "55") (name "Net-(IC4-4Y)") (class "Default")
      (node (ref "IC4") (pin "14") (pinfunction "4Y_14") (pintype "output"))
      (node (ref "MOTOR") (pin "6") (pinfunction "6_6") (pintype "passive"))
    )
    (net (code "56") (name "Net-(IC4-VCC2)") (class "Default")
      (node (ref "C9") (pin "2") (pinfunction "2_2") (pintype "passive"))
      (node (ref "IC4") (pin "8") (pinfunction "VCC2_8") (pintype "power_in"))
      (node (ref "JP2") (pin "2") (pinfunction "2_2") (pintype "passive"))
      (node (ref "MOTOR") (pin "2") (pinfunction "2_2") (pintype "passive"))
    )
    (net (code "57") (name "Net-(JP1-Pad1)") (class "Default")
      (node (ref "JP1") (pin "1") (pinfunction "1_1") (pintype "passive"))
      (node (ref "P1") (pin "2") (pinfunction "2_2") (pintype "passive"))
      (node (ref "R1") (pin "1") (pinfunction "1_1") (pintype "passive"))
      (node (ref "R2") (pin "1") (pinfunction "1_1") (pintype "passive"))
    )
    (net (code "58") (name "Net-(JP1B-2)") (class "Default")
      (node (ref "JP1") (pin "4") (pinfunction "2_4") (pintype "passive"))
      (node (ref "USB") (pin "2") (pinfunction "2_2") (pintype "passive"))
    )
    (net (code "59") (name "Net-(JP1C-2)") (class "Default")
      (node (ref "JP1") (pin "6") (pinfunction "2_6") (pintype "passive"))
      (node (ref "USB") (pin "3") (pinfunction "3_3") (pintype "passive"))
    )
    (net (code "60") (name "Net-(JP3B-1)") (class "Default")
      (node (ref "JP3") (pin "3") (pinfunction "1_3") (pintype "passive"))
      (node (ref "LD0") (pin "K") (pinfunction "C_K") (pintype "passive"))
      (node (ref "LD1") (pin "K") (pinfunction "C_K") (pintype "passive"))
      (node (ref "LD2") (pin "K") (pinfunction "C_K") (pintype "passive"))
      (node (ref "LD3") (pin "K") (pinfunction "C_K") (pintype "passive"))
    )
    (net (code "61") (name "Net-(LCD-LEDK)") (class "Default")
      (node (ref "LCD") (pin "16") (pinfunction "LEDK_16") (pintype "passive"))
      (node (ref "T1") (pin "3") (pinfunction "C_3") (pintype "passive"))
    )
    (net (code "62") (name "Net-(LCD-VO)") (class "Default")
      (node (ref "LCD") (pin "3") (pinfunction "VO_3") (pintype "input"))
      (node (ref "TR1") (pin "S") (pinfunction "S_S") (pintype "passive"))
      (node (ref "TR1") (pin "S1") (pinfunction "S1_S1") (pintype "passive"))
    )
    (net (code "63") (name "Net-(LD0-PadA)") (class "Default")
      (node (ref "LD0") (pin "A") (pinfunction "A_A") (pintype "passive"))
      (node (ref "R16") (pin "2") (pinfunction "2_2") (pintype "passive"))
    )
    (net (code "64") (name "Net-(LD1-PadA)") (class "Default")
      (node (ref "LD1") (pin "A") (pinfunction "A_A") (pintype "passive"))
      (node (ref "R15") (pin "2") (pinfunction "2_2") (pintype "passive"))
    )
    (net (code "65") (name "Net-(LD2-PadA)") (class "Default")
      (node (ref "LD2") (pin "A") (pinfunction "A_A") (pintype "passive"))
      (node (ref "R14") (pin "2") (pinfunction "2_2") (pintype "passive"))
    )
    (net (code "66") (name "Net-(LD3-PadA)") (class "Default")
      (node (ref "LD3") (pin "A") (pinfunction "A_A") (pintype "passive"))
      (node (ref "R13") (pin "2") (pinfunction "2_2") (pintype "passive"))
    )
    (net (code "67") (name "Net-(LD4-C)") (class "Default")
      (node (ref "JP3") (pin "1") (pinfunction "1_1") (pintype "passive"))
      (node (ref "LD4") (pin "K") (pinfunction "C_K") (pintype "passive"))
      (node (ref "LD5") (pin "K") (pinfunction "C_K") (pintype "passive"))
      (node (ref "LD6") (pin "K") (pinfunction "C_K") (pintype "passive"))
      (node (ref "LD7") (pin "K") (pinfunction "C_K") (pintype "passive"))
    )
    (net (code "68") (name "Net-(LD4-PadA)") (class "Default")
      (node (ref "LD4") (pin "A") (pinfunction "A_A") (pintype "passive"))
      (node (ref "R12") (pin "2") (pinfunction "2_2") (pintype "passive"))
    )
    (net (code "69") (name "Net-(LD5-PadA)") (class "Default")
      (node (ref "LD5") (pin "A") (pinfunction "A_A") (pintype "passive"))
      (node (ref "R11") (pin "2") (pinfunction "2_2") (pintype "passive"))
    )
    (net (code "70") (name "Net-(LD6-PadA)") (class "Default")
      (node (ref "LD6") (pin "A") (pinfunction "A_A") (pintype "passive"))
      (node (ref "R10") (pin "2") (pinfunction "2_2") (pintype "passive"))
    )
    (net (code "71") (name "Net-(LD7-PadA)") (class "Default")
      (node (ref "LD7") (pin "A") (pinfunction "A_A") (pintype "passive"))
      (node (ref "R9") (pin "2") (pinfunction "2_2") (pintype "passive"))
    )
    (net (code "72") (name "Net-(LD8-C)") (class "Default")
      (node (ref "LD8") (pin "K") (pinfunction "C_K") (pintype "passive"))
      (node (ref "R4") (pin "2") (pinfunction "2_2") (pintype "passive"))
    )
    (net (code "73") (name "Net-(P1-Pad1)") (class "Default")
      (node (ref "P1") (pin "1") (pinfunction "1_1") (pintype "passive"))
      (node (ref "USB") (pin "1") (pinfunction "1_1") (pintype "passive"))
    )
    (net (code "74") (name "Net-(PROG-Pad1)") (class "Default")
      (node (ref "PROG") (pin "1") (pinfunction "1_1") (pintype "passive"))
      (node (ref "R17") (pin "2") (pinfunction "2_2") (pintype "passive"))
    )
    (net (code "75") (name "Net-(PROG-Pad5)") (class "Default")
      (node (ref "PROG") (pin "5") (pinfunction "5_5") (pintype "passive"))
      (node (ref "R18") (pin "2") (pinfunction "2_2") (pintype "passive"))
    )
    (net (code "76") (name "Net-(PROG-Pad9)") (class "Default")
      (node (ref "PROG") (pin "9") (pinfunction "9_9") (pintype "passive"))
      (node (ref "R7") (pin "2") (pinfunction "2_2") (pintype "passive"))
    )
    (net (code "77") (name "Net-(R20-Pad2)") (class "Default")
      (node (ref "R20") (pin "2") (pinfunction "2_2") (pintype "passive"))
      (node (ref "SERVO1") (pin "+") (pinfunction "+_+") (pintype "passive"))
      (node (ref "SERVO2") (pin "+") (pinfunction "+_+") (pintype "passive"))
    )
    (net (code "78") (name "Net-(S3-S)") (class "Default")
      (node (ref "R19") (pin "1") (pinfunction "1_1") (pintype "passive"))
      (node (ref "S3") (pin "1") (pinfunction "S_1") (pintype "passive"))
    )
    (net (code "79") (name "Net-(S4-S)") (class "Default")
      (node (ref "R6") (pin "1") (pinfunction "1_1") (pintype "passive"))
      (node (ref "S4") (pin "1") (pinfunction "S_1") (pintype "passive"))
    )
    (net (code "80") (name "Net-(T1-B)") (class "Default")
      (node (ref "R3") (pin "1") (pinfunction "1_1") (pintype "passive"))
      (node (ref "T1") (pin "2") (pinfunction "B_2") (pintype "passive"))
    )
    (net (code "81") (name "unconnected-(IC3A-R2OUT-Pad9)") (class "Default")
      (node (ref "IC3") (pin "9") (pinfunction "R2OUT_9") (pintype "output"))
    )
    (net (code "82") (name "unconnected-(IC3A-T2OUT-Pad7)") (class "Default")
      (node (ref "IC3") (pin "7") (pinfunction "T2OUT_7") (pintype "output"))
    )
    (net (code "83") (name "unconnected-(POWER-PadC)") (class "Default")
      (node (ref "POWER") (pin "C") (pinfunction "C_C") (pintype "passive"))
    )
    (net (code "84") (name "unconnected-(PROG-Pad8)") (class "Default")
      (node (ref "PROG") (pin "8") (pinfunction "8_8") (pintype "passive"))
    )
    (net (code "85") (name "unconnected-(S1-S1-Pad2)") (class "Default")
      (node (ref "S1") (pin "2") (pinfunction "S1_2") (pintype "passive"))
    )
    (net (code "86") (name "unconnected-(S2-S1-Pad2)") (class "Default")
      (node (ref "S2") (pin "2") (pinfunction "S1_2") (pintype "passive"))
    )
    (net (code "87") (name "unconnected-(S3-S1-Pad2)") (class "Default")
      (node (ref "S3") (pin "2") (pinfunction "S1_2") (pintype "passive"))
    )
    (net (code "88") (name "unconnected-(S4-S1-Pad2)") (class "Default")
      (node (ref "S4") (pin "2") (pinfunction "S1_2") (pintype "passive"))
    )
    (net (code "89") (name "unconnected-(S5-S1-Pad2)") (class "Default")
      (node (ref "S5") (pin "2") (pinfunction "S1_2") (pintype "passive"))
    )
    (net (code "90") (name "unconnected-(S6-S1-Pad2)") (class "Default")
      (node (ref "S6") (pin "2") (pinfunction "S1_2") (pintype "passive"))
    )
    (net (code "91") (name "unconnected-(SER-Pad1)") (class "Default")
      (node (ref "SER") (pin "1") (pinfunction "1_1") (pintype "passive"))
    )
    (net (code "92") (name "unconnected-(SER-Pad4)") (class "Default")
      (node (ref "SER") (pin "4") (pinfunction "4_4") (pintype "passive"))
    )
    (net (code "93") (name "unconnected-(SER-Pad6)") (class "Default")
      (node (ref "SER") (pin "6") (pinfunction "6_6") (pintype "passive"))
    )
    (net (code "94") (name "unconnected-(SER-Pad7)") (class "Default")
      (node (ref "SER") (pin "7") (pinfunction "7_7") (pintype "passive"))
    )
    (net (code "95") (name "unconnected-(SER-Pad8)") (class "Default")
      (node (ref "SER") (pin "8") (pinfunction "8_8") (pintype "passive"))
    )
    (net (code "96") (name "unconnected-(SER-Pad9)") (class "Default")
      (node (ref "SER") (pin "9") (pinfunction "9_9") (pintype "passive"))
    )
    (net (code "97") (name "unconnected-(SER-PadG1)") (class "Default")
      (node (ref "SER") (pin "G1") (pinfunction "G1_G1") (pintype "passive"))
    )
    (net (code "98") (name "unconnected-(SER-PadG2)") (class "Default")
      (node (ref "SER") (pin "G2") (pinfunction "G2_G2") (pintype "passive"))
    )
    (net (code "99") (name "unconnected-(USB-PadS1)") (class "Default")
      (node (ref "USB") (pin "S1") (pinfunction "S1_S1") (pintype "passive"))
    )
    (net (code "100") (name "unconnected-(USB-PadS2)") (class "Default")
      (node (ref "USB") (pin "S2") (pinfunction "S2_S2") (pintype "passive"))
    )
  )
)
